# IMU.net
KiCad netlist of a schematic drawn in Altium Designer
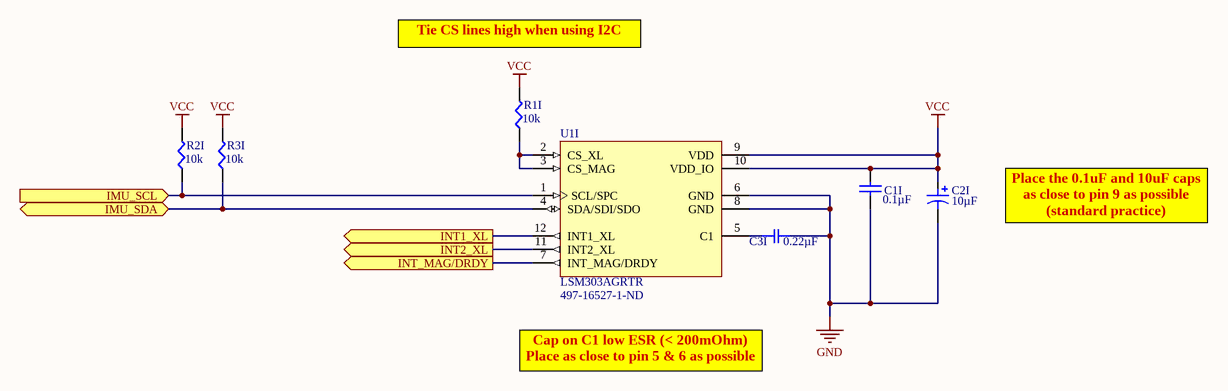
[diagram p0: IMU.SchDoc]

(export (version "E")
  (design (tool "Eeschema 10.0.6"))
  (components
    (comp (ref "C1I")
      (value "GCM188R71C104KA37D")
      (footprint "C0603N")
      (fields
        (field (name "HOUSEPART") "NO")
        (field (name "TOLERANCE") "±10%")
        (field (name "VOLTAGE") "16V")
        (field (name "CAPACITANCE") "0.1µF")
      )
      (libsource (lib "MF_Passives") (part "CAPACITOR_NP"))
    )
    (comp (ref "C2I")
      (value "10µF")
      (footprint "2917")
      (description "10µF 12.5V Aluminum Polymer Capacitor 2917 (7343 Metric) 60 mOhm 1000 Hrs @ 105°C")
      (fields (field (name "HOUSEPART") "NO") (field (name "MPN") "EEF-CD1B100R"))
      (libsource (lib "Passives") (part "CAPACITOR_P"))
    )
    (comp (ref "C3I")
      (value "0.22µF")
      (footprint "C0603N")
      (description "CAP CER 0.22UF 25V X7R 0603")
      (fields
        (field (name "DIGI-KEY PART NUMBER") "490-8017-1-ND")
        (field (name "PART NUMBER") "GCM188R71E224KA55J")
      )
      (libsource (lib "capacitor_murata_0603") (part "GCM188R71E224KA55J"))
    )
    (comp (ref "R1I")
      (value "10k")
      (footprint "SMD-0603-RES")
      (description "RES SMD 10K OHM 1% 1/10W 0603")
      (fields
        (field (name "PART NUMBER") "ERJ-3EKF1002V")
        (field (name "DIGI-KEY PART NUMBER") "P10.0KHCT-ND")
      )
      (libsource (lib "Panasonic_ERJ_0603") (part "ERJ-3EKF1002V"))
    )
    (comp (ref "R2I")
      (value "10k")
      (footprint "SMD-0603-RES")
      (description "RES SMD 10K OHM 1% 1/10W 0603")
      (fields
        (field (name "PART NUMBER") "ERJ-3EKF1002V")
        (field (name "DIGI-KEY PART NUMBER") "P10.0KHCT-ND")
      )
      (libsource (lib "Panasonic_ERJ_0603") (part "ERJ-3EKF1002V"))
    )
    (comp (ref "R3I")
      (value "10k")
      (footprint "SMD-0603-RES")
      (description "RES SMD 10K OHM 1% 1/10W 0603")
      (fields
        (field (name "PART NUMBER") "ERJ-3EKF1002V")
        (field (name "DIGI-KEY PART NUMBER") "P10.0KHCT-ND")
      )
      (libsource (lib "Panasonic_ERJ_0603") (part "ERJ-3EKF1002V"))
    )
    (comp (ref "U1I")
      (value "LSM303AGRTR")
      (footprint "LGA12R50P_200X200X100")
      (fields (field (name "SUPPLIER PART NUMBER 1") "497-16527-1-ND"))
      (libsource (lib "LSM303AGRTR") (part "CMP-98f6527696964731-1"))
    )
  )
  (nets
    (net (code "1") (name "/IMU_SCL") (class "Default")
      (node (ref "R2I") (pin "1") (pinfunction "1_1") (pintype "passive"))
      (node (ref "U1I") (pin "1") (pinfunction "SCL/SPC_1") (pintype "input"))
    )
    (net (code "2") (name "/IMU_SDA") (class "Default")
      (node (ref "R3I") (pin "1") (pinfunction "1_1") (pintype "passive"))
      (node (ref "U1I") (pin "4") (pinfunction "SDA/SDI/SDO_4") (pintype "bidirectional"))
    )
    (net (code "3") (name "/INT1_XL") (class "Default")
      (node (ref "U1I") (pin "12") (pinfunction "INT1_XL_12") (pintype "output"))
    )
    (net (code "4") (name "/INT2_XL") (class "Default")
      (node (ref "U1I") (pin "11") (pinfunction "INT2_XL_11") (pintype "output"))
    )
    (net (code "5") (name "/INT_MAG{slash}DRDY") (class "Default")
      (node (ref "U1I") (pin "7") (pinfunction "INT_MAG/DRDY_7") (pintype "output"))
    )
    (net (code "6") (name "GND") (class "Default")
      (node (ref "C1I") (pin "1") (pinfunction "1_1") (pintype "passive"))
      (node (ref "C2I") (pin "2") (pinfunction "2_2") (pintype "passive"))
      (node (ref "C3I") (pin "2") (pinfunction "2_2") (pintype "passive"))
      (node (ref "U1I") (pin "6") (pinfunction "GND_6") (pintype "power_in"))
      (node (ref "U1I") (pin "8") (pinfunction "GND_8") (pintype "power_in"))
    )
    (net (code "7") (name "Net-(U1I-C1)") (class "Default")
      (node (ref "C3I") (pin "1") (pinfunction "1_1") (pintype "passive"))
      (node (ref "U1I") (pin "5") (pinfunction "C1_5") (pintype "passive"))
    )
    (net (code "8") (name "Net-(U1I-CS_MAG)") (class "Default")
      (node (ref "R1I") (pin "1") (pinfunction "1_1") (pintype "passive"))
      (node (ref "U1I") (pin "2") (pinfunction "CS_XL_2") (pintype "input"))
      (node (ref "U1I") (pin "3") (pinfunction "CS_MAG_3") (pintype "input"))
    )
    (net (code "9") (name "VCC") (class "Default")
      (node (ref "C1I") (pin "2") (pinfunction "2_2") (pintype "passive"))
      (node (ref "C2I") (pin "1") (pinfunction "1_1") (pintype "passive"))
      (node (ref "R1I") (pin "2") (pinfunction "2_2") (pintype "passive"))
      (node (ref "R2I") (pin "2") (pinfunction "2_2") (pintype "passive"))
      (node (ref "R3I") (pin "2") (pinfunction "2_2") (pintype "passive"))
      (node (ref "U1I") (pin "10") (pinfunction "VDD_IO_10") (pintype "power_in"))
      (node (ref "U1I") (pin "9") (pinfunction "VDD_9") (pintype "power_in"))
    )
  )
)
